# MainBoard_V1p0_TEMP.net
KiCad netlist of a schematic drawn in Altium Designer
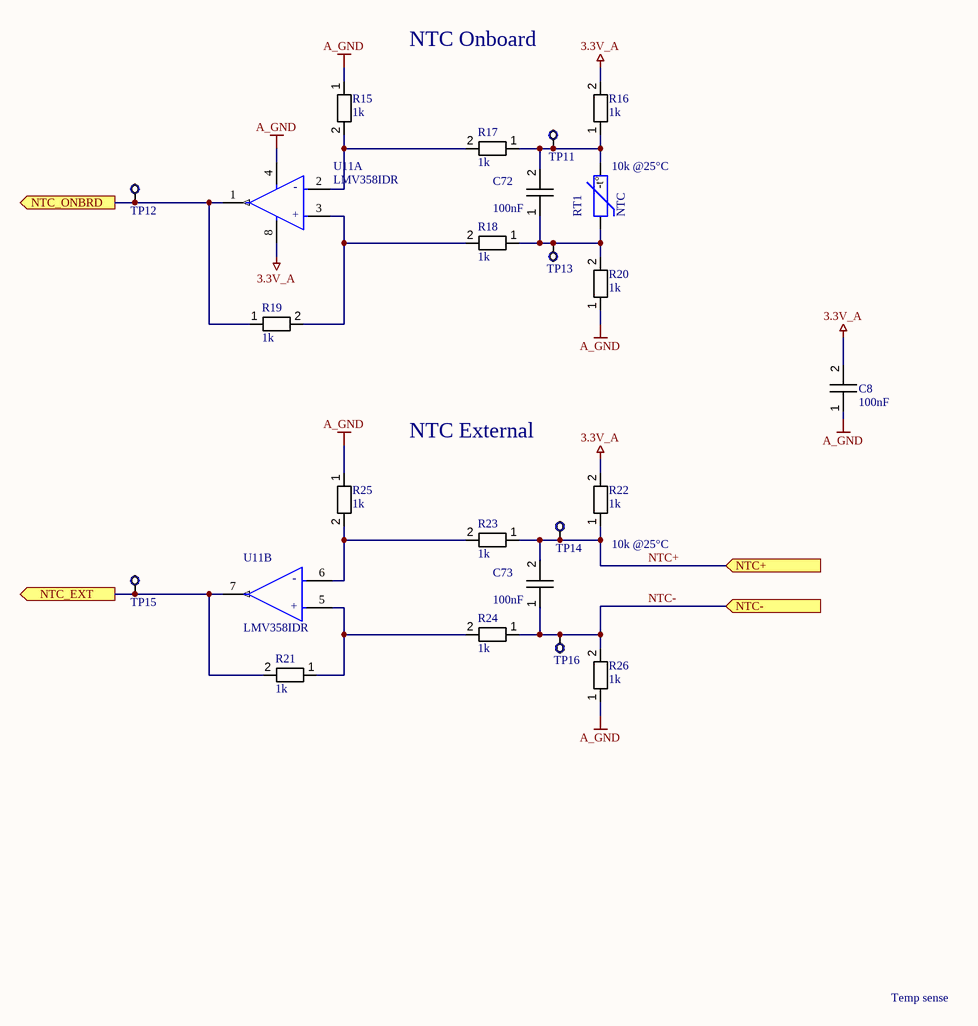
[diagram p0: MainBoard_V1p0_TEMP.SchDoc]

(export (version "E")
  (design (tool "Eeschema 10.0.6"))
  (components
    (comp (ref "C8") (value "100nF") (footprint "0805_C") (libsource (lib "Schlib1") (part "CAPACITOR")))
    (comp (ref "C72") (value "100nF") (footprint "0805_C") (libsource (lib "Schlib1") (part "CAPACITOR")))
    (comp (ref "C73") (value "100nF") (footprint "0805_C") (libsource (lib "Schlib1") (part "CAPACITOR")))
    (comp (ref "R15") (value "1k") (footprint "0805") (libsource (lib "Schlib1") (part "RESISTOR")))
    (comp (ref "R16") (value "1k") (footprint "0805") (libsource (lib "Schlib1") (part "RESISTOR")))
    (comp (ref "R17") (value "1k") (footprint "0805") (libsource (lib "Schlib1") (part "RESISTOR")))
    (comp (ref "R18") (value "1k") (footprint "0805") (libsource (lib "Schlib1") (part "RESISTOR")))
    (comp (ref "R19") (value "1k") (footprint "0805") (libsource (lib "Schlib1") (part "RESISTOR")))
    (comp (ref "R20") (value "1k") (footprint "0805") (libsource (lib "Schlib1") (part "RESISTOR")))
    (comp (ref "R21") (value "1k") (footprint "0805") (libsource (lib "Schlib1") (part "RESISTOR")))
    (comp (ref "R22") (value "1k") (footprint "0805") (libsource (lib "Schlib1") (part "RESISTOR")))
    (comp (ref "R23") (value "1k") (footprint "0805") (libsource (lib "Schlib1") (part "RESISTOR")))
    (comp (ref "R24") (value "1k") (footprint "0805") (libsource (lib "Schlib1") (part "RESISTOR")))
    (comp (ref "R25") (value "1k") (footprint "0805") (libsource (lib "Schlib1") (part "RESISTOR")))
    (comp (ref "R26") (value "1k") (footprint "0805") (libsource (lib "Schlib1") (part "RESISTOR")))
    (comp (ref "RT1") (value "NTC") (footprint "0805") (libsource (lib "Schlib1") (part "NTC")))
    (comp (ref "TP11") (value "?") (footprint "PAD_40") (libsource (lib "Schlib1") (part "TESTPOINT")))
    (comp (ref "TP12") (value "?") (footprint "PAD_40") (libsource (lib "Schlib1") (part "TESTPOINT")))
    (comp (ref "TP13") (value "?") (footprint "PAD_40") (libsource (lib "Schlib1") (part "TESTPOINT")))
    (comp (ref "TP14") (value "?") (footprint "PAD_40") (libsource (lib "Schlib1") (part "TESTPOINT")))
    (comp (ref "TP15") (value "?") (footprint "PAD_40") (libsource (lib "Schlib1") (part "TESTPOINT")))
    (comp (ref "TP16") (value "?") (footprint "PAD_40") (libsource (lib "Schlib1") (part "TESTPOINT")))
    (comp (ref "U11")
      (value "LMV358IDR")
      (footprint "SO-8")
      (description "IC OPAMP GP 2 CIRCUIT 8SOIC")
      (libsource (lib "ic_modules") (part "LMV358IDR"))
    )
  )
  (nets
    (net (code "1") (name "/NTC+") (class "Default")
      (node (ref "C73") (pin "2") (pinfunction "2_2") (pintype "passive"))
      (node (ref "R22") (pin "1") (pinfunction "0_1") (pintype "passive"))
      (node (ref "R23") (pin "1") (pinfunction "0_1") (pintype "passive"))
      (node (ref "TP14") (pin "1") (pinfunction "1_1") (pintype "passive"))
    )
    (net (code "2") (name "/NTC-") (class "Default")
      (node (ref "C73") (pin "1") (pinfunction "1_1") (pintype "passive"))
      (node (ref "R24") (pin "1") (pinfunction "0_1") (pintype "passive"))
      (node (ref "R26") (pin "2") (pinfunction "1_2") (pintype "passive"))
      (node (ref "TP16") (pin "1") (pinfunction "1_1") (pintype "passive"))
    )
    (net (code "3") (name "/NTC_EXT") (class "Default")
      (node (ref "R21") (pin "2") (pinfunction "1_2") (pintype "passive"))
      (node (ref "TP15") (pin "1") (pinfunction "1_1") (pintype "passive"))
      (node (ref "U11") (pin "7") (pinfunction "2OUT_7") (pintype "output"))
    )
    (net (code "4") (name "/NTC_ONBRD") (class "Default")
      (node (ref "R19") (pin "1") (pinfunction "0_1") (pintype "passive"))
      (node (ref "TP12") (pin "1") (pinfunction "1_1") (pintype "passive"))
      (node (ref "U11") (pin "1") (pinfunction "OUT_1") (pintype "output"))
    )
    (net (code "5") (name "3.3V_A") (class "Default")
      (node (ref "C8") (pin "2") (pinfunction "2_2") (pintype "passive"))
      (node (ref "R16") (pin "2") (pinfunction "1_2") (pintype "passive"))
      (node (ref "R22") (pin "2") (pinfunction "1_2") (pintype "passive"))
      (node (ref "U11") (pin "8") (pinfunction "VCC+_8") (pintype "power_in"))
    )
    (net (code "6") (name "A_GND") (class "Default")
      (node (ref "C8") (pin "1") (pinfunction "1_1") (pintype "passive"))
      (node (ref "R15") (pin "1") (pinfunction "0_1") (pintype "passive"))
      (node (ref "R20") (pin "1") (pinfunction "0_1") (pintype "passive"))
      (node (ref "R25") (pin "1") (pinfunction "0_1") (pintype "passive"))
      (node (ref "R26") (pin "1") (pinfunction "0_1") (pintype "passive"))
      (node (ref "U11") (pin "4") (pinfunction "GND_4") (pintype "power_in"))
    )
    (net (code "7") (name "Net-(R15-1)") (class "Default")
      (node (ref "R15") (pin "2") (pinfunction "1_2") (pintype "passive"))
      (node (ref "R17") (pin "2") (pinfunction "1_2") (pintype "passive"))
      (node (ref "U11") (pin "2") (pinfunction "1IN-_2") (pintype "tri_state"))
    )
    (net (code "8") (name "Net-(R16-0)") (class "Default")
      (node (ref "C72") (pin "2") (pinfunction "2_2") (pintype "passive"))
      (node (ref "R16") (pin "1") (pinfunction "0_1") (pintype "passive"))
      (node (ref "R17") (pin "1") (pinfunction "0_1") (pintype "passive"))
      (node (ref "RT1") (pin "2") (pintype "passive"))
      (node (ref "TP11") (pin "1") (pinfunction "1_1") (pintype "passive"))
    )
    (net (code "9") (name "Net-(R18-0)") (class "Default")
      (node (ref "C72") (pin "1") (pinfunction "1_1") (pintype "passive"))
      (node (ref "R18") (pin "1") (pinfunction "0_1") (pintype "passive"))
      (node (ref "R20") (pin "2") (pinfunction "1_2") (pintype "passive"))
      (node (ref "RT1") (pin "1") (pintype "passive"))
      (node (ref "TP13") (pin "1") (pinfunction "1_1") (pintype "passive"))
    )
    (net (code "10") (name "Net-(R18-1)") (class "Default")
      (node (ref "R18") (pin "2") (pinfunction "1_2") (pintype "passive"))
      (node (ref "R19") (pin "2") (pinfunction "1_2") (pintype "passive"))
      (node (ref "U11") (pin "3") (pinfunction "1IN+_3") (pintype "tri_state"))
    )
    (net (code "11") (name "Net-(R21-0)") (class "Default")
      (node (ref "R21") (pin "1") (pinfunction "0_1") (pintype "passive"))
      (node (ref "R24") (pin "2") (pinfunction "1_2") (pintype "passive"))
      (node (ref "U11") (pin "5") (pinfunction "2IN+_5") (pintype "tri_state"))
    )
    (net (code "12") (name "Net-(R23-1)") (class "Default")
      (node (ref "R23") (pin "2") (pinfunction "1_2") (pintype "passive"))
      (node (ref "R25") (pin "2") (pinfunction "1_2") (pintype "passive"))
      (node (ref "U11") (pin "6") (pinfunction "2IN-_6") (pintype "tri_state"))
    )
  )
)
